# SCH_esp32-4g-gateway_2026-08-06.net
KiCad netlist of a schematic drawn in EasyEDA
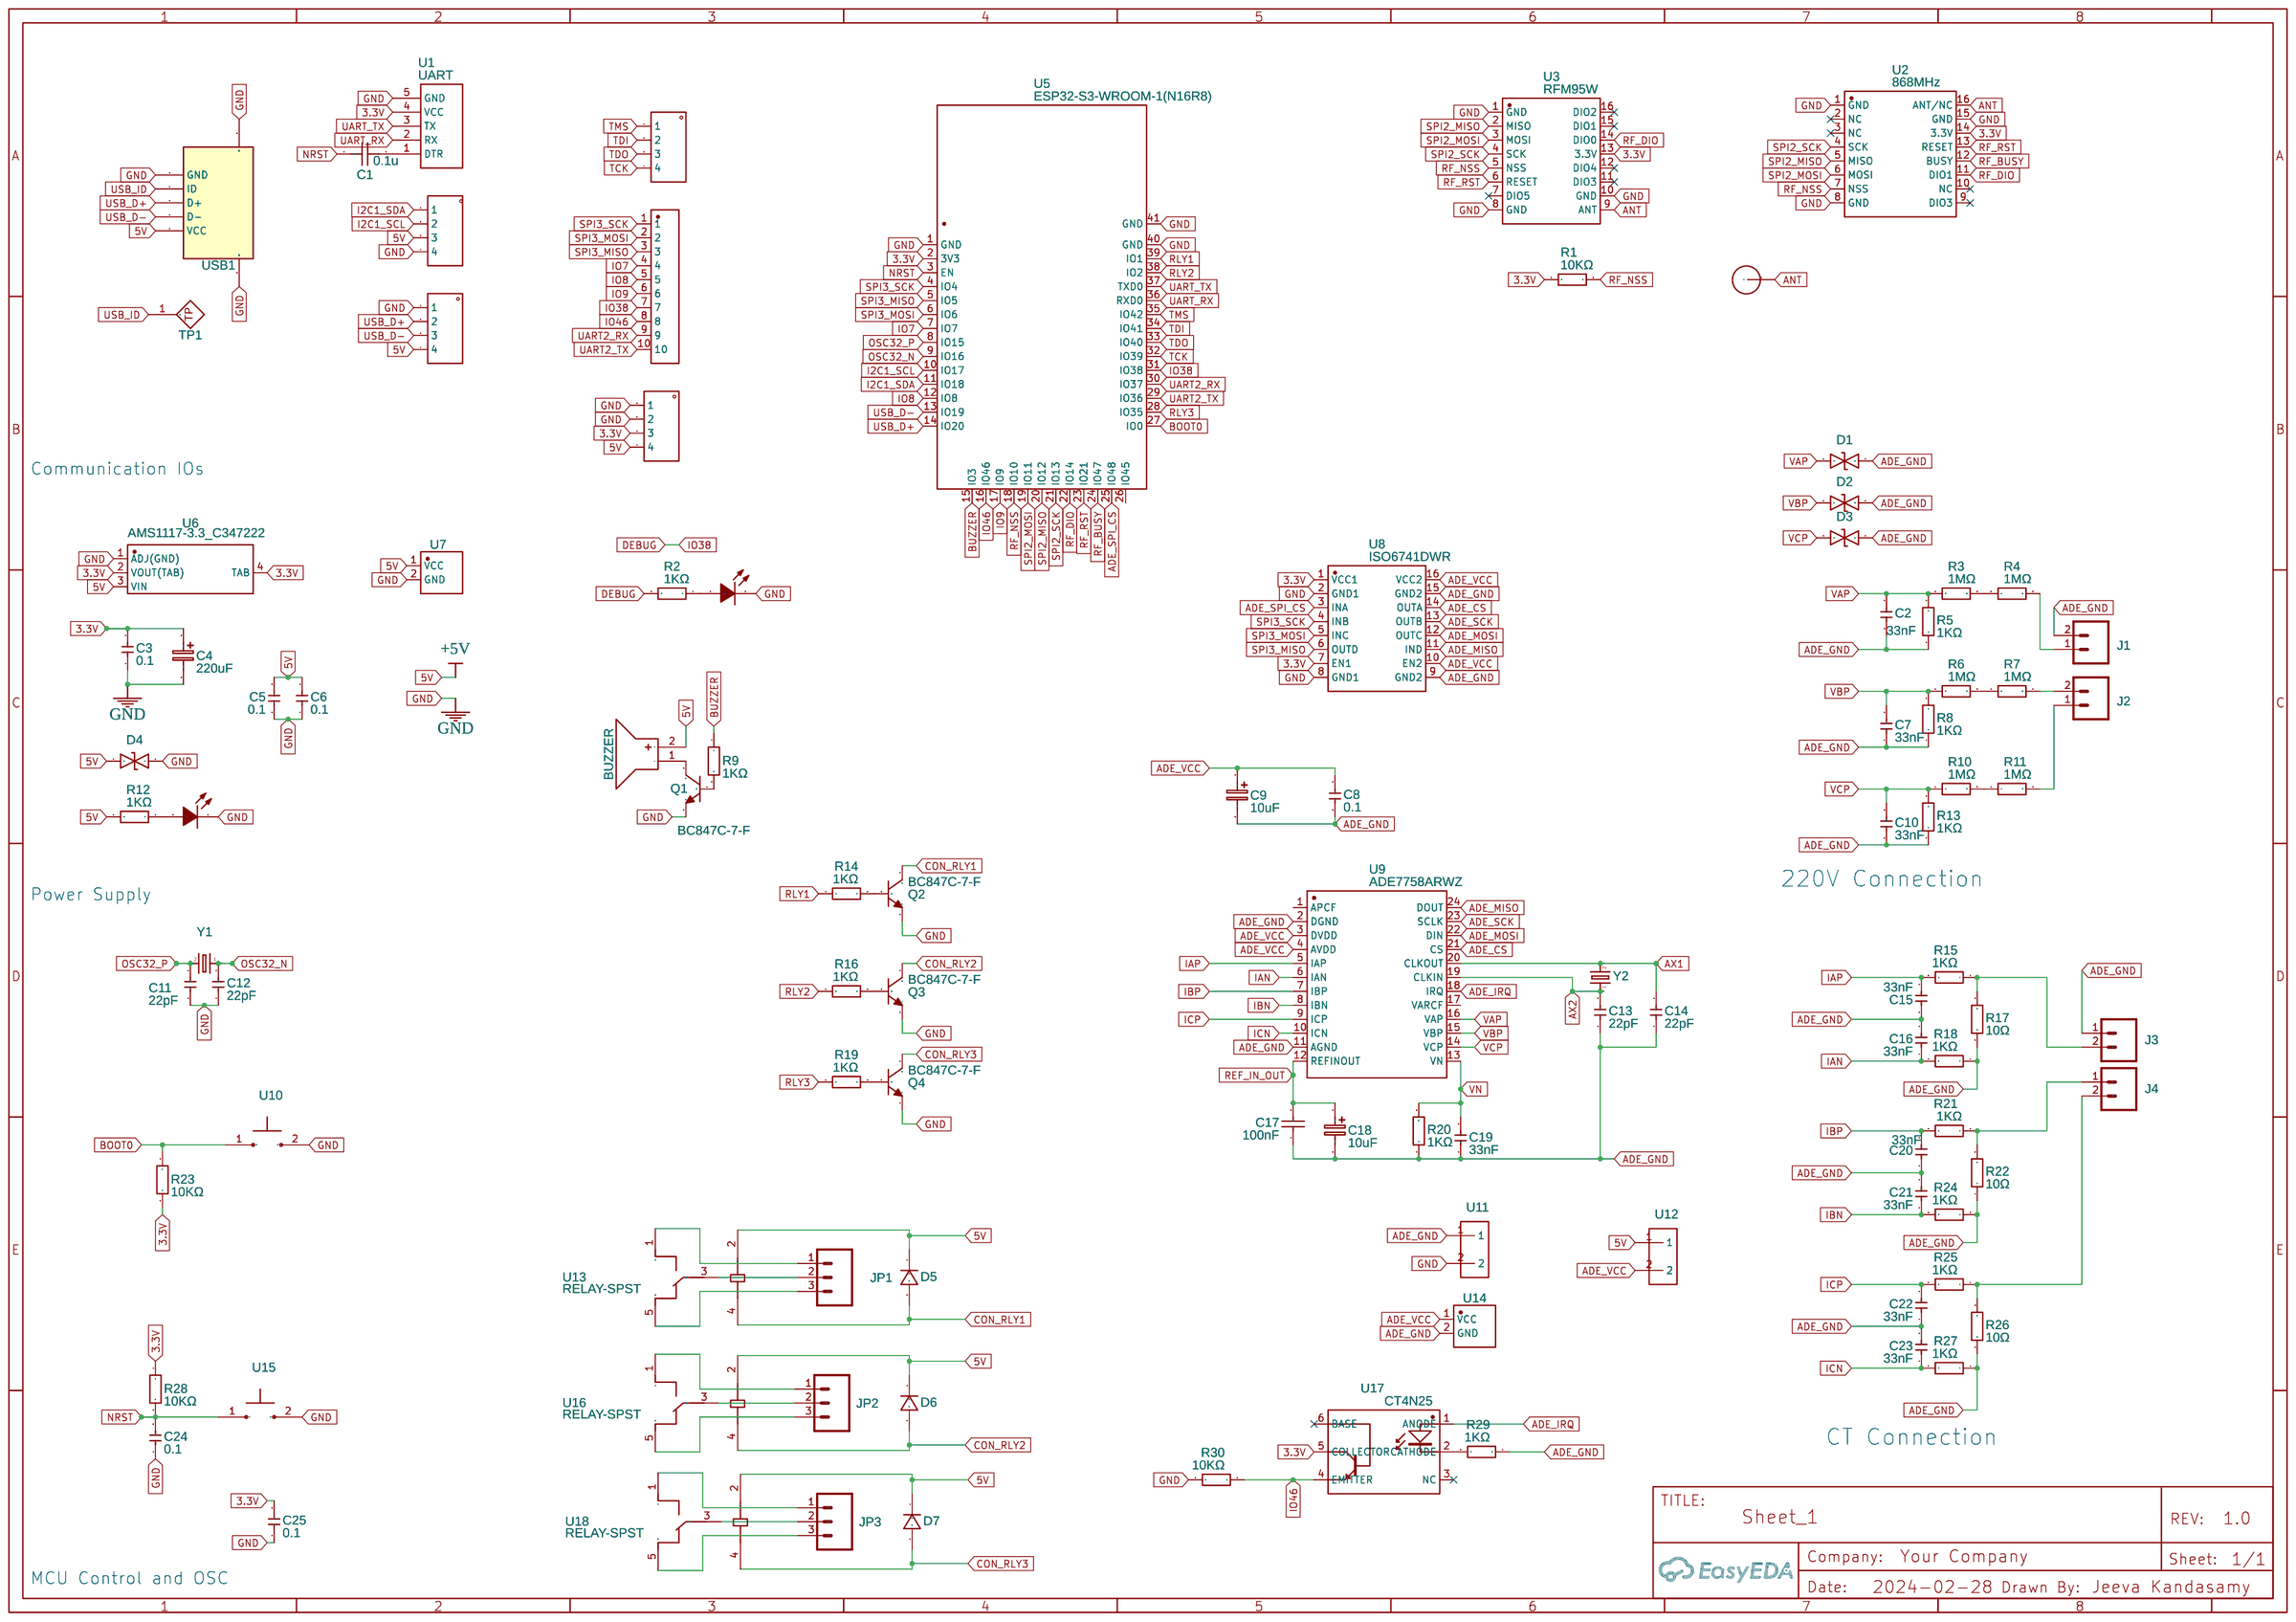
[diagram p0: schematic sheet]

(export (version "E")
  (design (tool "Eeschema 10.0.6"))
  (components
    (comp (ref "ANT1") (value "RFM12B_ANTENNA") (libsource (lib "") (part "RFM12B_ANTENNA")))
    (comp (ref "BUZZER")
      (value "BUZZER")
      (fields (field (name "Manufacturer Part") "buzzer"))
      (libsource (lib "") (part "BUZZER"))
    )
    (comp (ref "C1") (value "0.1u") (libsource (lib "") (part "C_0603_US")))
    (comp (ref "C2")
      (value "33nF")
      (fields (field (name "Manufacturer Part") "CC0603KRX7R9BB333"))
      (libsource (lib "") (part "Unknown_1345_-720"))
    )
    (comp (ref "C3")
      (value "0.1")
      (fields (field (name "Manufacturer Part") "CC0603JRNPO9BN220"))
      (libsource (lib "") (part "Unknown_85_-695"))
    )
    (comp (ref "C4")
      (value "220uF")
      (fields (field (name "Manufacturer Part") "JORGE TOURIS COMPANY"))
      (libsource (lib "") (part "My 10uF Capator"))
    )
    (comp (ref "C5")
      (value "0.1")
      (fields (field (name "Manufacturer Part") "CC0603JRNPO9BN220"))
      (libsource (lib "") (part "Unknown_190_-660"))
    )
    (comp (ref "C6")
      (value "0.1")
      (fields (field (name "Manufacturer Part") "CC0603JRNPO9BN220"))
      (libsource (lib "") (part "Unknown_210_-660"))
    )
    (comp (ref "C7")
      (value "33nF")
      (fields (field (name "Manufacturer Part") "CC0603KRX7R9BB333"))
      (libsource (lib "") (part "Unknown_1345_-640"))
    )
    (comp (ref "C8")
      (value "0.1")
      (fields (field (name "Manufacturer Part") "CC0603JRNPO9BN220"))
      (libsource (lib "") (part "Unknown_950_-590"))
    )
    (comp (ref "C9")
      (value "10uF")
      (fields (field (name "Manufacturer Part") "JORGE TOURIS COMPANY"))
      (libsource (lib "") (part "My 10uF Capator_2"))
    )
    (comp (ref "C10")
      (value "33nF")
      (fields (field (name "Manufacturer Part") "CC0603KRX7R9BB333"))
      (libsource (lib "") (part "Unknown_1345_-570"))
    )
    (comp (ref "C11")
      (value "22pF")
      (fields (field (name "Manufacturer Part") "CC0603JRNPO9BN220"))
      (libsource (lib "") (part "Unknown_130_-455"))
    )
    (comp (ref "C12")
      (value "22pF")
      (fields (field (name "Manufacturer Part") "CC0603JRNPO9BN220"))
      (libsource (lib "") (part "Unknown_150_-455"))
    )
    (comp (ref "C13")
      (value "22pF")
      (fields (field (name "Manufacturer Part") "CC0603JRNPO9BN220"))
      (libsource (lib "") (part "Unknown_1140_-435"))
    )
    (comp (ref "C14")
      (value "22pF")
      (fields (field (name "Manufacturer Part") "CC0603JRNPO9BN220"))
      (libsource (lib "") (part "Unknown_1180_-435"))
    )
    (comp (ref "C15")
      (value "33nF")
      (fields (field (name "Manufacturer Part") "CC0603KRX7R9BB333"))
      (libsource (lib "") (part "Unknown_1370_-435"))
    )
    (comp (ref "C16")
      (value "33nF")
      (fields (field (name "Manufacturer Part") "CC0603KRX7R9BB333"))
      (libsource (lib "") (part "Unknown_1370_-415"))
    )
    (comp (ref "C17")
      (value "100nF")
      (fields (field (name "Manufacturer Part") "0603B104K500NT") (field (name "Manufacturer") "FH"))
      (libsource (lib "") (part "Unknown_920_-355"))
    )
    (comp (ref "C18")
      (value "10uF")
      (fields (field (name "Manufacturer Part") "JORGE TOURIS COMPANY"))
      (libsource (lib "") (part "My 10uF Capator_1"))
    )
    (comp (ref "C19")
      (value "33nF")
      (fields (field (name "Manufacturer Part") "CC0603KRX7R9BB333"))
      (libsource (lib "") (part "Unknown_1040_-345"))
    )
    (comp (ref "C20")
      (value "33nF")
      (fields (field (name "Manufacturer Part") "CC0603KRX7R9BB333"))
      (libsource (lib "") (part "Unknown_1370_-335"))
    )
    (comp (ref "C21")
      (value "33nF")
      (fields (field (name "Manufacturer Part") "CC0603KRX7R9BB333"))
      (libsource (lib "") (part "Unknown_1370_-305"))
    )
    (comp (ref "C22")
      (value "33nF")
      (fields (field (name "Manufacturer Part") "CC0603KRX7R9BB333"))
      (libsource (lib "") (part "Unknown_1370_-225"))
    )
    (comp (ref "C23")
      (value "33nF")
      (fields (field (name "Manufacturer Part") "CC0603KRX7R9BB333"))
      (libsource (lib "") (part "Unknown_1370_-195"))
    )
    (comp (ref "C24")
      (value "0.1")
      (fields (field (name "Manufacturer Part") "CC0603JRNPO9BN220"))
      (libsource (lib "") (part "Unknown_105_-130"))
    )
    (comp (ref "C25")
      (value "0.1")
      (fields (field (name "Manufacturer Part") "CC0603JRNPO9BN220"))
      (libsource (lib "") (part "Unknown_190_-70"))
    )
    (comp (ref "CN1") (value "PINHEADER-4PIN") (libsource (lib "") (part "PINHEADER-4PIN")))
    (comp (ref "CN2") (value "PINHEADER-4PIN") (libsource (lib "") (part "PINHEADER-4PIN_1")))
    (comp (ref "CN3") (value "PINHEADER-4PIN") (libsource (lib "") (part "PINHEADER-4PIN")))
    (comp (ref "CN4") (value "PINHEADER-4PIN") (libsource (lib "") (part "PINHEADER-4PIN")))
    (comp (ref "D1")
      (value "P4SMA6.8CA_C139527")
      (fields (field (name "Manufacturer Part") "P4SMA6.8CA") (field (name "Manufacturer") "Yenji Elec"))
      (libsource (lib "") (part "P4SMA6.8CA_C139527"))
    )
    (comp (ref "D2")
      (value "P4SMA6.8CA_C139527")
      (fields (field (name "Manufacturer Part") "P4SMA6.8CA") (field (name "Manufacturer") "Yenji Elec"))
      (libsource (lib "") (part "P4SMA6.8CA_C139527"))
    )
    (comp (ref "D3")
      (value "P4SMA6.8CA_C139527")
      (fields (field (name "Manufacturer Part") "P4SMA6.8CA") (field (name "Manufacturer") "Yenji Elec"))
      (libsource (lib "") (part "P4SMA6.8CA_C139527"))
    )
    (comp (ref "D4")
      (value "P4SMA6.8CA_C139527")
      (fields (field (name "Manufacturer Part") "P4SMA6.8CA") (field (name "Manufacturer") "Yenji Elec"))
      (libsource (lib "") (part "P4SMA6.8CA_C139527"))
    )
    (comp (ref "D5")
      (value "1N4007GU")
      (fields (field (name "Manufacturer") "DIYI Elec Tech"))
      (libsource (lib "") (part "1N4007GU"))
    )
    (comp (ref "D6")
      (value "1N4007GU")
      (fields (field (name "Manufacturer") "DIYI Elec Tech"))
      (libsource (lib "") (part "1N4007GU"))
    )
    (comp (ref "D7")
      (value "1N4007GU")
      (fields (field (name "Manufacturer") "DIYI Elec Tech"))
      (libsource (lib "") (part "1N4007GU"))
    )
    (comp (ref "DEBUG")
      (value "3ARB9HCB")
      (fields (field (name "Manufacturer") "KENTO"))
      (libsource (lib "") (part "3ARB9HCB"))
    )
    (comp (ref "J1") (value "M02-SCREW-5MM") (libsource (lib "") (part "M02-SCREW-5MM_1")))
    (comp (ref "J2") (value "M02-SCREW-5MM") (libsource (lib "") (part "M02-SCREW-5MM_1")))
    (comp (ref "J3") (value "M02-SCREW-5MM") (libsource (lib "") (part "M02-SCREW-5MM")))
    (comp (ref "J4") (value "M02-SCREW-5MM") (libsource (lib "") (part "M02-SCREW-5MM")))
    (comp (ref "JP1") (value "M03-SCREW-5MM") (libsource (lib "") (part "M03-SCREW-5MM")))
    (comp (ref "JP2") (value "M03-SCREW-5MM") (libsource (lib "") (part "M03-SCREW-5MM")))
    (comp (ref "JP3") (value "M03-SCREW-5MM") (libsource (lib "") (part "M03-SCREW-5MM")))
    (comp (ref "POWER")
      (value "3ARB9HCB")
      (fields (field (name "Manufacturer") "KENTO"))
      (libsource (lib "") (part "3ARB9HCB_1"))
    )
    (comp (ref "Q1")
      (value "BC847C-7-F")
      (fields (field (name "Manufacturer") "DIODES(美台)"))
      (libsource (lib "") (part "BC847C-7-F_1"))
    )
    (comp (ref "Q2")
      (value "BC847C-7-F")
      (fields (field (name "Manufacturer") "DIODES(美台)"))
      (libsource (lib "") (part "BC847C-7-F"))
    )
    (comp (ref "Q3")
      (value "BC847C-7-F")
      (fields (field (name "Manufacturer") "DIODES(美台)"))
      (libsource (lib "") (part "BC847C-7-F"))
    )
    (comp (ref "Q4")
      (value "BC847C-7-F")
      (fields (field (name "Manufacturer") "DIODES(美台)"))
      (libsource (lib "") (part "BC847C-7-F"))
    )
    (comp (ref "R1")
      (value "10KΩ")
      (fields (field (name "Manufacturer Part") "0603WAF1001T5E") (field (name "Manufacturer") "UniOhm"))
      (libsource (lib "") (part "Unknown_1120_-955"))
    )
    (comp (ref "R2")
      (value "1KΩ")
      (fields (field (name "Manufacturer Part") "0603WAF1001T5E") (field (name "Manufacturer") "UniOhm"))
      (libsource (lib "") (part "Unknown_475_-730"))
    )
    (comp (ref "R3")
      (value "1MΩ")
      (fields (field (name "Manufacturer Part") "0603WAF1004T5E") (field (name "Manufacturer") "UniOhm"))
      (libsource (lib "") (part "Unknown_1395_-730"))
    )
    (comp (ref "R4")
      (value "1MΩ")
      (fields (field (name "Manufacturer Part") "0603WAF1004T5E") (field (name "Manufacturer") "UniOhm"))
      (libsource (lib "") (part "Unknown_1435_-730"))
    )
    (comp (ref "R5")
      (value "1KΩ")
      (fields (field (name "Manufacturer Part") "0603WAF1001T5E") (field (name "Manufacturer") "UniOhm"))
      (libsource (lib "") (part "Unknown_1375_-710"))
    )
    (comp (ref "R6")
      (value "1MΩ")
      (fields (field (name "Manufacturer Part") "0603WAF1004T5E") (field (name "Manufacturer") "UniOhm"))
      (libsource (lib "") (part "Unknown_1395_-660"))
    )
    (comp (ref "R7")
      (value "1MΩ")
      (fields (field (name "Manufacturer Part") "0603WAF1004T5E") (field (name "Manufacturer") "UniOhm"))
      (libsource (lib "") (part "Unknown_1435_-660"))
    )
    (comp (ref "R8")
      (value "1KΩ")
      (fields (field (name "Manufacturer Part") "0603WAF1001T5E") (field (name "Manufacturer") "UniOhm"))
      (libsource (lib "") (part "Unknown_1375_-640"))
    )
    (comp (ref "R9")
      (value "1KΩ")
      (fields (field (name "Manufacturer Part") "0603WAF1001T5E") (field (name "Manufacturer") "UniOhm"))
      (libsource (lib "") (part "Unknown_505_-610"))
    )
    (comp (ref "R10")
      (value "1MΩ")
      (fields (field (name "Manufacturer Part") "0603WAF1004T5E") (field (name "Manufacturer") "UniOhm"))
      (libsource (lib "") (part "Unknown_1395_-590"))
    )
    (comp (ref "R11")
      (value "1MΩ")
      (fields (field (name "Manufacturer Part") "0603WAF1004T5E") (field (name "Manufacturer") "UniOhm"))
      (libsource (lib "") (part "Unknown_1435_-590"))
    )
    (comp (ref "R12")
      (value "1KΩ")
      (fields (field (name "Manufacturer Part") "0603WAF1001T5E") (field (name "Manufacturer") "UniOhm"))
      (libsource (lib "") (part "Unknown_90_-570"))
    )
    (comp (ref "R13")
      (value "1KΩ")
      (fields (field (name "Manufacturer Part") "0603WAF1001T5E") (field (name "Manufacturer") "UniOhm"))
      (libsource (lib "") (part "Unknown_1375_-570"))
    )
    (comp (ref "R14")
      (value "1KΩ")
      (fields (field (name "Manufacturer Part") "0603WAF1001T5E") (field (name "Manufacturer") "UniOhm"))
      (libsource (lib "") (part "Unknown_600_-515"))
    )
    (comp (ref "R15")
      (value "1KΩ")
      (fields (field (name "Manufacturer Part") "0603WAF1001T5E") (field (name "Manufacturer") "UniOhm"))
      (libsource (lib "") (part "Unknown_1390_-455"))
    )
    (comp (ref "R16")
      (value "1KΩ")
      (fields (field (name "Manufacturer Part") "0603WAF1001T5E") (field (name "Manufacturer") "UniOhm"))
      (libsource (lib "") (part "Unknown_600_-445"))
    )
    (comp (ref "R17")
      (value "10Ω")
      (fields (field (name "Manufacturer Part") "0603WAF100JT5E") (field (name "Manufacturer") "UniOhm"))
      (libsource (lib "") (part "Unknown_1410_-425"))
    )
    (comp (ref "R18")
      (value "1KΩ")
      (fields (field (name "Manufacturer Part") "0603WAF1001T5E") (field (name "Manufacturer") "UniOhm"))
      (libsource (lib "") (part "Unknown_1390_-395"))
    )
    (comp (ref "R19")
      (value "1KΩ")
      (fields (field (name "Manufacturer Part") "0603WAF1001T5E") (field (name "Manufacturer") "UniOhm"))
      (libsource (lib "") (part "Unknown_600_-380"))
    )
    (comp (ref "R20")
      (value "1KΩ")
      (fields (field (name "Manufacturer Part") "0603WAF1001T5E") (field (name "Manufacturer") "UniOhm"))
      (libsource (lib "") (part "Unknown_1010_-345"))
    )
    (comp (ref "R21")
      (value "1KΩ")
      (fields (field (name "Manufacturer Part") "0603WAF1001T5E") (field (name "Manufacturer") "UniOhm"))
      (libsource (lib "") (part "Unknown_1390_-345"))
    )
    (comp (ref "R22")
      (value "10Ω")
      (fields (field (name "Manufacturer Part") "0603WAF100JT5E") (field (name "Manufacturer") "UniOhm"))
      (libsource (lib "") (part "Unknown_1410_-315"))
    )
    (comp (ref "R23")
      (value "10KΩ")
      (fields (field (name "Manufacturer Part") "0603WAF1001T5E") (field (name "Manufacturer") "UniOhm"))
      (libsource (lib "") (part "Unknown_110_-310"))
    )
    (comp (ref "R24")
      (value "1KΩ")
      (fields (field (name "Manufacturer Part") "0603WAF1001T5E") (field (name "Manufacturer") "UniOhm"))
      (libsource (lib "") (part "Unknown_1390_-285"))
    )
    (comp (ref "R25")
      (value "1KΩ")
      (fields (field (name "Manufacturer Part") "0603WAF1001T5E") (field (name "Manufacturer") "UniOhm"))
      (libsource (lib "") (part "Unknown_1390_-235"))
    )
    (comp (ref "R26")
      (value "10Ω")
      (fields (field (name "Manufacturer Part") "0603WAF100JT5E") (field (name "Manufacturer") "UniOhm"))
      (libsource (lib "") (part "Unknown_1410_-205"))
    )
    (comp (ref "R27")
      (value "1KΩ")
      (fields (field (name "Manufacturer Part") "0603WAF1001T5E") (field (name "Manufacturer") "UniOhm"))
      (libsource (lib "") (part "Unknown_1390_-175"))
    )
    (comp (ref "R28")
      (value "10KΩ")
      (fields (field (name "Manufacturer Part") "0603WAF1001T5E") (field (name "Manufacturer") "UniOhm"))
      (libsource (lib "") (part "Unknown_105_-160"))
    )
    (comp (ref "R29")
      (value "1KΩ")
      (fields (field (name "Manufacturer Part") "0603WAF1001T5E") (field (name "Manufacturer") "UniOhm"))
      (libsource (lib "") (part "Unknown_1055_-115"))
    )
    (comp (ref "R30")
      (value "10KΩ")
      (fields (field (name "Manufacturer Part") "0603WAF1001T5E") (field (name "Manufacturer") "UniOhm"))
      (libsource (lib "") (part "Unknown_865_-95"))
    )
    (comp (ref "TP1") (value "Test Point") (libsource (lib "") (part "Test Point")))
    (comp (ref "U1")
      (value "UART")
      (fields (field (name "Manufacturer Part") "CP2102 UART"))
      (libsource (lib "") (part "Arduino-UART"))
    )
    (comp (ref "U2")
      (value "868MHz")
      (fields
        (field (name "Manufacturer Part") "DL-LLCC68-S-868")
        (field (name "Manufacturer") "DreamLNK(骏晔科技)")
      )
      (libsource (lib "") (part "DL-LLCC68-S-868"))
    )
    (comp (ref "U3") (value "RFM95W") (libsource (lib "") (part "RFM95W")))
    (comp (ref "U4")
      (value "Pin Header 1x10Pin 2.54mm 10P")
      (libsource (lib "") (part "Pin Header 1x10Pin 2.54mm 10P"))
    )
    (comp (ref "U5")
      (value "ESP32-S3-WROOM-1(N16R8)")
      (fields
        (field (name "Manufacturer Part") "ESP32-S3-WROOM-1-N16R8")
        (field (name "Manufacturer") "ESPRESSIF(乐鑫)")
      )
      (libsource (lib "") (part "ESP32-S3-WROOM-1(N16R8)"))
    )
    (comp (ref "U6")
      (value "AMS1117-3.3_C347222")
      (fields
        (field (name "Manufacturer Part") "AMS1117-3.3")
        (field (name "Manufacturer") "Youtai Semiconductor Co., Ltd.")
      )
      (libsource (lib "") (part "AMS1117-3.3_C347222"))
    )
    (comp (ref "U7") (value "2 Pin Header") (libsource (lib "") (part "2 Pin Header")))
    (comp (ref "U8") (value "ISO6741DWR") (libsource (lib "") (part "ISO6741DWR")))
    (comp (ref "U9")
      (value "ADE7758ARWZ")
      (fields (field (name "Manufacturer Part") "?"))
      (libsource (lib "") (part "Unknown_980_-515"))
    )
    (comp (ref "U10")
      (value "SMD Tactile Switch 3x6x2.5")
      (libsource (lib "") (part "SMD Tactile Switch 3x6x2.5"))
    )
    (comp (ref "U11") (value "Jumper - 5MM") (libsource (lib "") (part "Jumper - 5MM")))
    (comp (ref "U12") (value "Jumper - 5MM") (libsource (lib "") (part "Jumper - 5MM")))
    (comp (ref "U13")
      (value "RELAY-SPST")
      (fields (field (name "Manufacturer Part") "Relay-SPST"))
      (libsource (lib "") (part "RELAY-SPST"))
    )
    (comp (ref "U14") (value "2 Pin Header") (libsource (lib "") (part "2 Pin Header")))
    (comp (ref "U15")
      (value "SMD Tactile Switch 3x6x2.5")
      (libsource (lib "") (part "SMD Tactile Switch 3x6x2.5"))
    )
    (comp (ref "U16")
      (value "RELAY-SPST")
      (fields (field (name "Manufacturer Part") "Relay-SPST"))
      (libsource (lib "") (part "RELAY-SPST"))
    )
    (comp (ref "U17")
      (value "CT4N25")
      (fields (field (name "Manufacturer Part") "4N25") (field (name "Manufacturer") "CT MICRO"))
      (libsource (lib "") (part "CT4N25"))
    )
    (comp (ref "U18")
      (value "RELAY-SPST")
      (fields (field (name "Manufacturer Part") "Relay-SPST"))
      (libsource (lib "") (part "RELAY-SPST"))
    )
    (comp (ref "USB1")
      (value "U-F-M5SW-Y-3")
      (fields (field (name "Manufacturer") "韩国韩荣"))
      (libsource (lib "") (part "U-F-M5SW-Y-3"))
    )
    (comp (ref "Y1")
      (value "CRYSTAL 10MHz")
      (fields (field (name "Manufacturer Part") "?"))
      (libsource (lib "") (part "Unknown_140_-465"))
    )
    (comp (ref "Y2")
      (value "CRYSTAL 10MHz")
      (fields (field (name "Manufacturer Part") "?"))
      (libsource (lib "") (part "Unknown_1140_-455"))
    )
  )
  (nets
    (net (code "1") (name "3.3V") (class "Default")
      (node (ref "C25") (pin "2") (pinfunction "2_2") (pintype "unspecified"))
      (node (ref "C3") (pin "2") (pinfunction "2_2") (pintype "unspecified"))
      (node (ref "C4") (pin "1") (pinfunction "1_1") (pintype "unspecified"))
      (node (ref "CN4") (pin "3") (pinfunction "3_3") (pintype "input"))
      (node (ref "R1") (pin "2") (pinfunction "2_2") (pintype "input"))
      (node (ref "R23") (pin "2") (pinfunction "2_2") (pintype "input"))
      (node (ref "R28") (pin "1") (pinfunction "1_1") (pintype "input"))
      (node (ref "U1") (pin "4") (pinfunction "VCC_4") (pintype "passive"))
      (node (ref "U17") (pin "5") (pinfunction "COLLECTOR_5") (pintype "unspecified"))
      (node (ref "U2") (pin "14") (pinfunction "3.3V_14") (pintype "unspecified"))
      (node (ref "U3") (pin "13") (pinfunction "3.3V_13") (pintype "unspecified"))
      (node (ref "U5") (pin "2") (pinfunction "3V3_2") (pintype "unspecified"))
      (node (ref "U6") (pin "2") (pinfunction "VOUT(TAB)_2") (pintype "unspecified"))
      (node (ref "U6") (pin "4") (pinfunction "TAB_4") (pintype "unspecified"))
      (node (ref "U8") (pin "1") (pinfunction "VCC1_1") (pintype "unspecified"))
      (node (ref "U8") (pin "7") (pinfunction "EN1_7") (pintype "unspecified"))
    )
    (net (code "2") (name "5V") (class "Default")
      (node (ref "BUZZER") (pin "2") (pinfunction "+_2") (pintype "unspecified"))
      (node (ref "C5") (pin "2") (pinfunction "2_2") (pintype "unspecified"))
      (node (ref "C6") (pin "2") (pinfunction "2_2") (pintype "unspecified"))
      (node (ref "CN2") (pin "3") (pinfunction "3_3") (pintype "input"))
      (node (ref "CN3") (pin "4") (pinfunction "4_4") (pintype "input"))
      (node (ref "CN4") (pin "4") (pinfunction "4_4") (pintype "input"))
      (node (ref "D4") (pin "2") (pinfunction "2_2") (pintype "unspecified"))
      (node (ref "D5") (pin "1") (pinfunction "1_1") (pintype "unspecified"))
      (node (ref "D6") (pin "1") (pinfunction "1_1") (pintype "unspecified"))
      (node (ref "D7") (pin "1") (pinfunction "1_1") (pintype "unspecified"))
      (node (ref "R12") (pin "2") (pinfunction "2_2") (pintype "input"))
      (node (ref "U12") (pin "1") (pinfunction "1_1") (pintype "unspecified"))
      (node (ref "U13") (pin "2") (pinfunction "2_2") (pintype "unspecified"))
      (node (ref "U16") (pin "2") (pinfunction "2_2") (pintype "unspecified"))
      (node (ref "U18") (pin "2") (pinfunction "2_2") (pintype "unspecified"))
      (node (ref "U6") (pin "3") (pinfunction "VIN_3") (pintype "unspecified"))
      (node (ref "U7") (pin "1") (pinfunction "VCC_1") (pintype "unspecified"))
      (node (ref "USB1") (pin "1") (pinfunction "VCC_1") (pintype "input"))
    )
    (net (code "3") (name "ADE_CS") (class "Default")
      (node (ref "U8") (pin "14") (pinfunction "OUTA_14") (pintype "unspecified"))
      (node (ref "U9") (pin "21") (pinfunction "CS_21") (pintype "unspecified"))
    )
    (net (code "4") (name "ADE_GND") (class "Default")
      (node (ref "C10") (pin "1") (pinfunction "1_1") (pintype "unspecified"))
      (node (ref "C13") (pin "1") (pinfunction "1_1") (pintype "unspecified"))
      (node (ref "C14") (pin "1") (pinfunction "1_1") (pintype "unspecified"))
      (node (ref "C15") (pin "2") (pinfunction "2_2") (pintype "unspecified"))
      (node (ref "C16") (pin "2") (pinfunction "2_2") (pintype "unspecified"))
      (node (ref "C17") (pin "1") (pinfunction "1_1") (pintype "input"))
      (node (ref "C18") (pin "2") (pinfunction "2_2") (pintype "unspecified"))
      (node (ref "C19") (pin "1") (pinfunction "1_1") (pintype "unspecified"))
      (node (ref "C2") (pin "1") (pinfunction "1_1") (pintype "unspecified"))
      (node (ref "C20") (pin "1") (pinfunction "1_1") (pintype "unspecified"))
      (node (ref "C21") (pin "2") (pinfunction "2_2") (pintype "unspecified"))
      (node (ref "C22") (pin "1") (pinfunction "1_1") (pintype "unspecified"))
      (node (ref "C23") (pin "2") (pinfunction "2_2") (pintype "unspecified"))
      (node (ref "C7") (pin "1") (pinfunction "1_1") (pintype "unspecified"))
      (node (ref "C8") (pin "1") (pinfunction "1_1") (pintype "unspecified"))
      (node (ref "C9") (pin "2") (pinfunction "2_2") (pintype "unspecified"))
      (node (ref "D1") (pin "1") (pinfunction "1_1") (pintype "unspecified"))
      (node (ref "D2") (pin "1") (pinfunction "1_1") (pintype "unspecified"))
      (node (ref "D3") (pin "1") (pinfunction "1_1") (pintype "unspecified"))
      (node (ref "J1") (pin "2") (pinfunction "2_2") (pintype "bidirectional"))
      (node (ref "J3") (pin "1") (pinfunction "1_1") (pintype "bidirectional"))
      (node (ref "R13") (pin "1") (pinfunction "1_1") (pintype "input"))
      (node (ref "R17") (pin "1") (pinfunction "1_1") (pintype "input"))
      (node (ref "R18") (pin "1") (pinfunction "1_1") (pintype "input"))
      (node (ref "R20") (pin "1") (pinfunction "1_1") (pintype "input"))
      (node (ref "R22") (pin "1") (pinfunction "1_1") (pintype "input"))
      (node (ref "R24") (pin "1") (pinfunction "1_1") (pintype "input"))
      (node (ref "R26") (pin "1") (pinfunction "1_1") (pintype "input"))
      (node (ref "R27") (pin "1") (pinfunction "1_1") (pintype "input"))
      (node (ref "R29") (pin "1") (pinfunction "1_1") (pintype "input"))
      (node (ref "R5") (pin "1") (pinfunction "1_1") (pintype "input"))
      (node (ref "R8") (pin "1") (pinfunction "1_1") (pintype "input"))
      (node (ref "U11") (pin "1") (pinfunction "1_1") (pintype "unspecified"))
      (node (ref "U14") (pin "2") (pinfunction "GND_2") (pintype "unspecified"))
      (node (ref "U8") (pin "15") (pinfunction "GND2_15") (pintype "unspecified"))
      (node (ref "U8") (pin "9") (pinfunction "GND2_9") (pintype "unspecified"))
      (node (ref "U9") (pin "11") (pinfunction "AGND_11") (pintype "unspecified"))
      (node (ref "U9") (pin "2") (pinfunction "DGND_2") (pintype "unspecified"))
    )
    (net (code "5") (name "ADE_IRQ") (class "Default")
      (node (ref "U17") (pin "1") (pinfunction "ANODE_1") (pintype "unspecified"))
      (node (ref "U9") (pin "18") (pinfunction "IRQ_18") (pintype "unspecified"))
    )
    (net (code "6") (name "ADE_MISO") (class "Default")
      (node (ref "U8") (pin "11") (pinfunction "IND_11") (pintype "unspecified"))
      (node (ref "U9") (pin "24") (pinfunction "DOUT_24") (pintype "unspecified"))
    )
    (net (code "7") (name "ADE_MOSI") (class "Default")
      (node (ref "U8") (pin "12") (pinfunction "OUTC_12") (pintype "unspecified"))
      (node (ref "U9") (pin "22") (pinfunction "DIN_22") (pintype "unspecified"))
    )
    (net (code "8") (name "ADE_SCK") (class "Default")
      (node (ref "U8") (pin "13") (pinfunction "OUTB_13") (pintype "unspecified"))
      (node (ref "U9") (pin "23") (pinfunction "SCLK_23") (pintype "unspecified"))
    )
    (net (code "9") (name "ADE_SPI_CS") (class "Default")
      (node (ref "U5") (pin "25") (pinfunction "IO48_25") (pintype "unspecified"))
      (node (ref "U8") (pin "3") (pinfunction "INA_3") (pintype "unspecified"))
    )
    (net (code "10") (name "ADE_VCC") (class "Default")
      (node (ref "C8") (pin "2") (pinfunction "2_2") (pintype "unspecified"))
      (node (ref "C9") (pin "1") (pinfunction "1_1") (pintype "unspecified"))
      (node (ref "U12") (pin "2") (pinfunction "2_2") (pintype "unspecified"))
      (node (ref "U14") (pin "1") (pinfunction "VCC_1") (pintype "unspecified"))
      (node (ref "U8") (pin "10") (pinfunction "EN2_10") (pintype "unspecified"))
      (node (ref "U8") (pin "16") (pinfunction "VCC2_16") (pintype "unspecified"))
      (node (ref "U9") (pin "3") (pinfunction "DVDD_3") (pintype "unspecified"))
      (node (ref "U9") (pin "4") (pinfunction "AVDD_4") (pintype "unspecified"))
    )
    (net (code "11") (name "ANT") (class "Default")
      (node (ref "ANT1") (pin "P$1") (pinfunction "1_P$1") (pintype "bidirectional"))
      (node (ref "U2") (pin "16") (pinfunction "ANT/NC_16") (pintype "unspecified"))
      (node (ref "U3") (pin "9") (pinfunction "ANT_9") (pintype "unspecified"))
    )
    (net (code "12") (name "AX1") (class "Default")
      (node (ref "C14") (pin "2") (pinfunction "2_2") (pintype "unspecified"))
      (node (ref "U9") (pin "20") (pinfunction "CLKOUT_20") (pintype "unspecified"))
      (node (ref "Y2") (pin "2") (pinfunction "2_2") (pintype "unspecified"))
    )
    (net (code "13") (name "AX2") (class "Default")
      (node (ref "C13") (pin "2") (pinfunction "2_2") (pintype "unspecified"))
      (node (ref "U9") (pin "19") (pinfunction "CLKIN_19") (pintype "unspecified"))
      (node (ref "Y2") (pin "1") (pinfunction "1_1") (pintype "unspecified"))
    )
    (net (code "14") (name "BOOT0") (class "Default")
      (node (ref "R23") (pin "1") (pinfunction "1_1") (pintype "input"))
      (node (ref "U10") (pin "1") (pinfunction "1_1") (pintype "unspecified"))
      (node (ref "U5") (pin "27") (pinfunction "IO0_27") (pintype "unspecified"))
    )
    (net (code "15") (name "BUZZER") (class "Default")
      (node (ref "R9") (pin "1") (pinfunction "1_1") (pintype "input"))
      (node (ref "U5") (pin "15") (pinfunction "IO3_15") (pintype "unspecified"))
    )
    (net (code "16") (name "CON_RLY1") (class "Default")
      (node (ref "D5") (pin "2") (pinfunction "2_2") (pintype "unspecified"))
      (node (ref "Q2") (pin "3") (pinfunction "C_3") (pintype "unspecified"))
      (node (ref "U13") (pin "4") (pinfunction "4_4") (pintype "unspecified"))
    )
    (net (code "17") (name "CON_RLY2") (class "Default")
      (node (ref "D6") (pin "2") (pinfunction "2_2") (pintype "unspecified"))
      (node (ref "Q3") (pin "3") (pinfunction "C_3") (pintype "unspecified"))
      (node (ref "U16") (pin "4") (pinfunction "4_4") (pintype "unspecified"))
    )
    (net (code "18") (name "CON_RLY3") (class "Default")
      (node (ref "D7") (pin "2") (pinfunction "2_2") (pintype "unspecified"))
      (node (ref "Q4") (pin "3") (pinfunction "C_3") (pintype "unspecified"))
      (node (ref "U18") (pin "4") (pinfunction "4_4") (pintype "unspecified"))
    )
    (net (code "19") (name "DEBUG") (class "Default")
      (node (ref "R2") (pin "2") (pinfunction "2_2") (pintype "input"))
      (node (ref "U4") (pin "7") (pinfunction "7_7") (pintype "unspecified"))
      (node (ref "U5") (pin "31") (pinfunction "IO38_31") (pintype "unspecified"))
    )
    (net (code "20") (name "GND") (class "Default")
      (node (ref "C11") (pin "1") (pinfunction "1_1") (pintype "unspecified"))
      (node (ref "C12") (pin "1") (pinfunction "1_1") (pintype "unspecified"))
      (node (ref "C24") (pin "1") (pinfunction "1_1") (pintype "unspecified"))
      (node (ref "C25") (pin "1") (pinfunction "1_1") (pintype "unspecified"))
      (node (ref "C3") (pin "1") (pinfunction "1_1") (pintype "unspecified"))
      (node (ref "C4") (pin "2") (pinfunction "2_2") (pintype "unspecified"))
      (node (ref "C5") (pin "1") (pinfunction "1_1") (pintype "unspecified"))
      (node (ref "C6") (pin "1") (pinfunction "1_1") (pintype "unspecified"))
      (node (ref "CN2") (pin "4") (pinfunction "4_4") (pintype "input"))
      (node (ref "CN3") (pin "1") (pinfunction "1_1") (pintype "input"))
      (node (ref "CN4") (pin "1") (pinfunction "1_1") (pintype "input"))
      (node (ref "CN4") (pin "2") (pinfunction "2_2") (pintype "input"))
      (node (ref "D4") (pin "1") (pinfunction "1_1") (pintype "unspecified"))
      (node (ref "DEBUG") (pin "2") (pinfunction "K_2") (pintype "unspecified"))
      (node (ref "POWER") (pin "2") (pinfunction "K_2") (pintype "unspecified"))
      (node (ref "Q1") (pin "2") (pinfunction "E_2") (pintype "unspecified"))
      (node (ref "Q2") (pin "2") (pinfunction "E_2") (pintype "unspecified"))
      (node (ref "Q3") (pin "2") (pinfunction "E_2") (pintype "unspecified"))
      (node (ref "Q4") (pin "2") (pinfunction "E_2") (pintype "unspecified"))
      (node (ref "R30") (pin "2") (pinfunction "2_2") (pintype "input"))
      (node (ref "U1") (pin "5") (pinfunction "GND_5") (pintype "passive"))
      (node (ref "U10") (pin "2") (pinfunction "2_2") (pintype "unspecified"))
      (node (ref "U11") (pin "2") (pinfunction "2_2") (pintype "unspecified"))
      (node (ref "U15") (pin "2") (pinfunction "2_2") (pintype "unspecified"))
      (node (ref "U2") (pin "1") (pinfunction "GND_1") (pintype "unspecified"))
      (node (ref "U2") (pin "15") (pinfunction "GND_15") (pintype "unspecified"))
      (node (ref "U2") (pin "8") (pinfunction "GND_8") (pintype "unspecified"))
      (node (ref "U3") (pin "1") (pinfunction "GND_1") (pintype "unspecified"))
      (node (ref "U3") (pin "10") (pinfunction "GND_10") (pintype "unspecified"))
      (node (ref "U3") (pin "8") (pinfunction "GND_8") (pintype "unspecified"))
      (node (ref "U5") (pin "1") (pinfunction "GND_1") (pintype "unspecified"))
      (node (ref "U5") (pin "40") (pinfunction "GND_40") (pintype "unspecified"))
      (node (ref "U5") (pin "41") (pinfunction "GND_41") (pintype "unspecified"))
      (node (ref "U6") (pin "1") (pinfunction "ADJ(GND)_1") (pintype "unspecified"))
      (node (ref "U7") (pin "2") (pinfunction "GND_2") (pintype "unspecified"))
      (node (ref "U8") (pin "2") (pinfunction "GND1_2") (pintype "unspecified"))
      (node (ref "U8") (pin "8") (pinfunction "GND1_8") (pintype "unspecified"))
      (node (ref "USB1") (pin "0") (pinfunction "SHLD_0") (pintype "input"))
      (node (ref "USB1") (pin "5") (pinfunction "GND_5") (pintype "input"))
    )
    (net (code "21") (name "I2C1_SCL") (class "Default")
      (node (ref "CN2") (pin "2") (pinfunction "2_2") (pintype "input"))
      (node (ref "U5") (pin "10") (pinfunction "IO17_10") (pintype "unspecified"))
    )
    (net (code "22") (name "I2C1_SDA") (class "Default")
      (node (ref "CN2") (pin "1") (pinfunction "1_1") (pintype "input"))
      (node (ref "U5") (pin "11") (pinfunction "IO18_11") (pintype "unspecified"))
    )
    (net (code "23") (name "IAN") (class "Default")
      (node (ref "C16") (pin "1") (pinfunction "1_1") (pintype "unspecified"))
      (node (ref "R18") (pin "2") (pinfunction "2_2") (pintype "input"))
      (node (ref "U9") (pin "6") (pinfunction "IAN_6") (pintype "unspecified"))
    )
    (net (code "24") (name "IAP") (class "Default")
      (node (ref "C15") (pin "1") (pinfunction "1_1") (pintype "unspecified"))
      (node (ref "R15") (pin "2") (pinfunction "2_2") (pintype "input"))
      (node (ref "U9") (pin "5") (pinfunction "IAP_5") (pintype "unspecified"))
    )
    (net (code "25") (name "IBN") (class "Default")
      (node (ref "C21") (pin "1") (pinfunction "1_1") (pintype "unspecified"))
      (node (ref "R24") (pin "2") (pinfunction "2_2") (pintype "input"))
      (node (ref "U9") (pin "8") (pinfunction "IBN_8") (pintype "unspecified"))
    )
    (net (code "26") (name "IBP") (class "Default")
      (node (ref "C20") (pin "2") (pinfunction "2_2") (pintype "unspecified"))
      (node (ref "R21") (pin "2") (pinfunction "2_2") (pintype "input"))
      (node (ref "U9") (pin "7") (pinfunction "IBP_7") (pintype "unspecified"))
    )
    (net (code "27") (name "ICN") (class "Default")
      (node (ref "C23") (pin "1") (pinfunction "1_1") (pintype "unspecified"))
      (node (ref "R27") (pin "2") (pinfunction "2_2") (pintype "input"))
      (node (ref "U9") (pin "10") (pinfunction "ICN_10") (pintype "unspecified"))
    )
    (net (code "28") (name "ICP") (class "Default")
      (node (ref "C22") (pin "2") (pinfunction "2_2") (pintype "unspecified"))
      (node (ref "R25") (pin "2") (pinfunction "2_2") (pintype "input"))
      (node (ref "U9") (pin "9") (pinfunction "ICP_9") (pintype "unspecified"))
    )
    (net (code "29") (name "IO7") (class "Default")
      (node (ref "U4") (pin "4") (pinfunction "4_4") (pintype "unspecified"))
      (node (ref "U5") (pin "7") (pinfunction "IO7_7") (pintype "unspecified"))
    )
    (net (code "30") (name "IO8") (class "Default")
      (node (ref "U4") (pin "5") (pinfunction "5_5") (pintype "unspecified"))
      (node (ref "U5") (pin "12") (pinfunction "IO8_12") (pintype "unspecified"))
    )
    (net (code "31") (name "IO9") (class "Default")
      (node (ref "U4") (pin "6") (pinfunction "6_6") (pintype "unspecified"))
      (node (ref "U5") (pin "17") (pinfunction "IO9_17") (pintype "unspecified"))
    )
    (net (code "32") (name "IO46") (class "Default")
      (node (ref "R30") (pin "1") (pinfunction "1_1") (pintype "input"))
      (node (ref "U17") (pin "4") (pinfunction "EMITTER_4") (pintype "unspecified"))
      (node (ref "U4") (pin "8") (pinfunction "8_8") (pintype "unspecified"))
      (node (ref "U5") (pin "16") (pinfunction "IO46_16") (pintype "unspecified"))
    )
    (net (code "33") (name "NRST") (class "Default")
      (node (ref "C1") (pin "1") (pinfunction "1_1") (pintype "unspecified"))
      (node (ref "C24") (pin "2") (pinfunction "2_2") (pintype "unspecified"))
      (node (ref "R28") (pin "2") (pinfunction "2_2") (pintype "input"))
      (node (ref "U15") (pin "1") (pinfunction "1_1") (pintype "unspecified"))
      (node (ref "U5") (pin "3") (pinfunction "EN_3") (pintype "unspecified"))
    )
    (net (code "34") (name "Net-(BUZZER--)") (class "Default")
      (node (ref "BUZZER") (pin "1") (pinfunction "-_1") (pintype "unspecified"))
      (node (ref "Q1") (pin "3") (pinfunction "C_3") (pintype "unspecified"))
    )
    (net (code "35") (name "Net-(DEBUG-A)") (class "Default")
      (node (ref "DEBUG") (pin "1") (pinfunction "A_1") (pintype "unspecified"))
      (node (ref "R2") (pin "1") (pinfunction "1_1") (pintype "input"))
    )
    (net (code "36") (name "Net-(J1-Pad1)") (class "Default")
      (node (ref "J1") (pin "1") (pinfunction "1_1") (pintype "bidirectional"))
      (node (ref "R4") (pin "2") (pinfunction "2_2") (pintype "input"))
    )
    (net (code "37") (name "Net-(J2-Pad1)") (class "Default")
      (node (ref "J2") (pin "1") (pinfunction "1_1") (pintype "bidirectional"))
      (node (ref "R11") (pin "2") (pinfunction "2_2") (pintype "input"))
    )
    (net (code "38") (name "Net-(J2-Pad2)") (class "Default")
      (node (ref "J2") (pin "2") (pinfunction "2_2") (pintype "bidirectional"))
      (node (ref "R7") (pin "2") (pinfunction "2_2") (pintype "input"))
    )
    (net (code "39") (name "Net-(J3-Pad2)") (class "Default")
      (node (ref "J3") (pin "2") (pinfunction "2_2") (pintype "bidirectional"))
      (node (ref "R15") (pin "1") (pinfunction "1_1") (pintype "input"))
      (node (ref "R17") (pin "2") (pinfunction "2_2") (pintype "input"))
    )
    (net (code "40") (name "Net-(J4-Pad1)") (class "Default")
      (node (ref "J4") (pin "1") (pinfunction "1_1") (pintype "bidirectional"))
      (node (ref "R21") (pin "1") (pinfunction "1_1") (pintype "input"))
      (node (ref "R22") (pin "2") (pinfunction "2_2") (pintype "input"))
    )
    (net (code "41") (name "Net-(J4-Pad2)") (class "Default")
      (node (ref "J4") (pin "2") (pinfunction "2_2") (pintype "bidirectional"))
      (node (ref "R25") (pin "1") (pinfunction "1_1") (pintype "input"))
      (node (ref "R26") (pin "2") (pinfunction "2_2") (pintype "input"))
    )
    (net (code "42") (name "Net-(JP1-Pad1)") (class "Default")
      (node (ref "JP1") (pin "1") (pinfunction "1_1") (pintype "bidirectional"))
      (node (ref "U13") (pin "1") (pinfunction "1_1") (pintype "unspecified"))
    )
    (net (code "43") (name "Net-(JP1-Pad2)") (class "Default")
      (node (ref "JP1") (pin "2") (pinfunction "2_2") (pintype "bidirectional"))
      (node (ref "U13") (pin "3") (pinfunction "3_3") (pintype "unspecified"))
    )
    (net (code "44") (name "Net-(JP1-Pad3)") (class "Default")
      (node (ref "JP1") (pin "3") (pinfunction "3_3") (pintype "bidirectional"))
      (node (ref "U13") (pin "5") (pinfunction "5_5") (pintype "unspecified"))
    )
    (net (code "45") (name "Net-(JP2-Pad1)") (class "Default")
      (node (ref "JP2") (pin "1") (pinfunction "1_1") (pintype "bidirectional"))
      (node (ref "U16") (pin "1") (pinfunction "1_1") (pintype "unspecified"))
    )
    (net (code "46") (name "Net-(JP2-Pad2)") (class "Default")
      (node (ref "JP2") (pin "2") (pinfunction "2_2") (pintype "bidirectional"))
      (node (ref "U16") (pin "3") (pinfunction "3_3") (pintype "unspecified"))
    )
    (net (code "47") (name "Net-(JP2-Pad3)") (class "Default")
      (node (ref "JP2") (pin "3") (pinfunction "3_3") (pintype "bidirectional"))
      (node (ref "U16") (pin "5") (pinfunction "5_5") (pintype "unspecified"))
    )
    (net (code "48") (name "Net-(JP3-Pad1)") (class "Default")
      (node (ref "JP3") (pin "1") (pinfunction "1_1") (pintype "bidirectional"))
      (node (ref "U18") (pin "1") (pinfunction "1_1") (pintype "unspecified"))
    )
    (net (code "49") (name "Net-(JP3-Pad2)") (class "Default")
      (node (ref "JP3") (pin "2") (pinfunction "2_2") (pintype "bidirectional"))
      (node (ref "U18") (pin "3") (pinfunction "3_3") (pintype "unspecified"))
    )
    (net (code "50") (name "Net-(JP3-Pad3)") (class "Default")
      (node (ref "JP3") (pin "3") (pinfunction "3_3") (pintype "bidirectional"))
      (node (ref "U18") (pin "5") (pinfunction "5_5") (pintype "unspecified"))
    )
    (net (code "51") (name "Net-(POWER-A)") (class "Default")
      (node (ref "POWER") (pin "1") (pinfunction "A_1") (pintype "unspecified"))
      (node (ref "R12") (pin "1") (pinfunction "1_1") (pintype "input"))
    )
    (net (code "52") (name "Net-(Q1-B)") (class "Default")
      (node (ref "Q1") (pin "1") (pinfunction "B_1") (pintype "unspecified"))
      (node (ref "R9") (pin "2") (pinfunction "2_2") (pintype "input"))
    )
    (net (code "53") (name "Net-(Q2-B)") (class "Default")
      (node (ref "Q2") (pin "1") (pinfunction "B_1") (pintype "unspecified"))
      (node (ref "R14") (pin "2") (pinfunction "2_2") (pintype "input"))
    )
    (net (code "54") (name "Net-(Q3-B)") (class "Default")
      (node (ref "Q3") (pin "1") (pinfunction "B_1") (pintype "unspecified"))
      (node (ref "R16") (pin "2") (pinfunction "2_2") (pintype "input"))
    )
    (net (code "55") (name "Net-(Q4-B)") (class "Default")
      (node (ref "Q4") (pin "1") (pinfunction "B_1") (pintype "unspecified"))
      (node (ref "R19") (pin "2") (pinfunction "2_2") (pintype "input"))
    )
    (net (code "56") (name "Net-(R3-Pad2)") (class "Default")
      (node (ref "R3") (pin "2") (pinfunction "2_2") (pintype "input"))
      (node (ref "R4") (pin "1") (pinfunction "1_1") (pintype "input"))
    )
    (net (code "57") (name "Net-(R6-Pad2)") (class "Default")
      (node (ref "R6") (pin "2") (pinfunction "2_2") (pintype "input"))
      (node (ref "R7") (pin "1") (pinfunction "1_1") (pintype "input"))
    )
    (net (code "58") (name "Net-(R10-Pad2)") (class "Default")
      (node (ref "R10") (pin "2") (pinfunction "2_2") (pintype "input"))
      (node (ref "R11") (pin "1") (pinfunction "1_1") (pintype "input"))
    )
    (net (code "59") (name "Net-(U1-DTR)") (class "Default")
      (node (ref "C1") (pin "2") (pinfunction "2_2") (pintype "unspecified"))
      (node (ref "U1") (pin "1") (pinfunction "DTR_1") (pintype "output"))
    )
    (net (code "60") (name "Net-(U17-CATHODE)") (class "Default")
      (node (ref "R29") (pin "2") (pinfunction "2_2") (pintype "input"))
      (node (ref "U17") (pin "2") (pinfunction "CATHODE_2") (pintype "unspecified"))
    )
    (net (code "61") (name "OSC32_N") (class "Default")
      (node (ref "C12") (pin "2") (pinfunction "2_2") (pintype "unspecified"))
      (node (ref "U5") (pin "9") (pinfunction "IO16_9") (pintype "unspecified"))
      (node (ref "Y1") (pin "1") (pinfunction "1_1") (pintype "unspecified"))
    )
    (net (code "62") (name "OSC32_P") (class "Default")
      (node (ref "C11") (pin "2") (pinfunction "2_2") (pintype "unspecified"))
      (node (ref "U5") (pin "8") (pinfunction "IO15_8") (pintype "unspecified"))
      (node (ref "Y1") (pin "2") (pinfunction "2_2") (pintype "unspecified"))
    )
    (net (code "63") (name "REF_IN_OUT") (class "Default")
      (node (ref "C17") (pin "2") (pinfunction "2_2") (pintype "input"))
      (node (ref "C18") (pin "1") (pinfunction "1_1") (pintype "unspecified"))
      (node (ref "U9") (pin "12") (pinfunction "REFINOUT_12") (pintype "unspecified"))
    )
    (net (code "64") (name "RF_BUSY") (class "Default")
      (node (ref "U2") (pin "12") (pinfunction "BUSY_12") (pintype "unspecified"))
      (node (ref "U5") (pin "24") (pinfunction "IO47_24") (pintype "unspecified"))
    )
    (net (code "65") (name "RF_DIO") (class "Default")
      (node (ref "U2") (pin "11") (pinfunction "DIO1_11") (pintype "unspecified"))
      (node (ref "U3") (pin "14") (pinfunction "DIO0_14") (pintype "unspecified"))
      (node (ref "U5") (pin "22") (pinfunction "IO14_22") (pintype "unspecified"))
    )
    (net (code "66") (name "RF_NSS") (class "Default")
      (node (ref "R1") (pin "1") (pinfunction "1_1") (pintype "input"))
      (node (ref "U2") (pin "7") (pinfunction "NSS_7") (pintype "unspecified"))
      (node (ref "U3") (pin "5") (pinfunction "NSS_5") (pintype "unspecified"))
      (node (ref "U5") (pin "18") (pinfunction "IO10_18") (pintype "unspecified"))
    )
    (net (code "67") (name "RF_RST") (class "Default")
      (node (ref "U2") (pin "13") (pinfunction "RESET_13") (pintype "unspecified"))
      (node (ref "U3") (pin "6") (pinfunction "RESET_6") (pintype "unspecified"))
      (node (ref "U5") (pin "23") (pinfunction "IO21_23") (pintype "unspecified"))
    )
    (net (code "68") (name "RLY1") (class "Default")
      (node (ref "R14") (pin "1") (pinfunction "1_1") (pintype "input"))
      (node (ref "U5") (pin "39") (pinfunction "IO1_39") (pintype "unspecified"))
    )
    (net (code "69") (name "RLY2") (class "Default")
      (node (ref "R16") (pin "1") (pinfunction "1_1") (pintype "input"))
      (node (ref "U5") (pin "38") (pinfunction "IO2_38") (pintype "unspecified"))
    )
    (net (code "70") (name "RLY3") (class "Default")
      (node (ref "R19") (pin "1") (pinfunction "1_1") (pintype "input"))
      (node (ref "U5") (pin "28") (pinfunction "IO35_28") (pintype "unspecified"))
    )
    (net (code "71") (name "SPI2_MISO") (class "Default")
      (node (ref "U2") (pin "5") (pinfunction "MISO_5") (pintype "unspecified"))
      (node (ref "U3") (pin "2") (pinfunction "MISO_2") (pintype "unspecified"))
      (node (ref "U5") (pin "20") (pinfunction "IO12_20") (pintype "unspecified"))
    )
    (net (code "72") (name "SPI2_MOSI") (class "Default")
      (node (ref "U2") (pin "6") (pinfunction "MOSI_6") (pintype "unspecified"))
      (node (ref "U3") (pin "3") (pinfunction "MOSI_3") (pintype "unspecified"))
      (node (ref "U5") (pin "19") (pinfunction "IO11_19") (pintype "unspecified"))
    )
    (net (code "73") (name "SPI2_SCK") (class "Default")
      (node (ref "U2") (pin "4") (pinfunction "SCK_4") (pintype "unspecified"))
      (node (ref "U3") (pin "4") (pinfunction "SCK_4") (pintype "unspecified"))
      (node (ref "U5") (pin "21") (pinfunction "IO13_21") (pintype "unspecified"))
    )
    (net (code "74") (name "SPI3_MISO") (class "Default")
      (node (ref "U4") (pin "3") (pinfunction "3_3") (pintype "unspecified"))
      (node (ref "U5") (pin "5") (pinfunction "IO5_5") (pintype "unspecified"))
      (node (ref "U8") (pin "6") (pinfunction "OUTD_6") (pintype "unspecified"))
    )
    (net (code "75") (name "SPI3_MOSI") (class "Default")
      (node (ref "U4") (pin "2") (pinfunction "2_2") (pintype "unspecified"))
      (node (ref "U5") (pin "6") (pinfunction "IO6_6") (pintype "unspecified"))
      (node (ref "U8") (pin "5") (pinfunction "INC_5") (pintype "unspecified"))
    )
    (net (code "76") (name "SPI3_SCK") (class "Default")
      (node (ref "U4") (pin "1") (pinfunction "1_1") (pintype "unspecified"))
      (node (ref "U5") (pin "4") (pinfunction "IO4_4") (pintype "unspecified"))
      (node (ref "U8") (pin "4") (pinfunction "INB_4") (pintype "unspecified"))
    )
    (net (code "77") (name "TCK") (class "Default")
      (node (ref "CN1") (pin "4") (pinfunction "4_4") (pintype "input"))
      (node (ref "U5") (pin "32") (pinfunction "IO39_32") (pintype "unspecified"))
    )
    (net (code "78") (name "TDI") (class "Default")
      (node (ref "CN1") (pin "2") (pinfunction "2_2") (pintype "input"))
      (node (ref "U5") (pin "34") (pinfunction "IO41_34") (pintype "unspecified"))
    )
    (net (code "79") (name "TDO") (class "Default")
      (node (ref "CN1") (pin "3") (pinfunction "3_3") (pintype "input"))
      (node (ref "U5") (pin "33") (pinfunction "IO40_33") (pintype "unspecified"))
    )
    (net (code "80") (name "TMS") (class "Default")
      (node (ref "CN1") (pin "1") (pinfunction "1_1") (pintype "input"))
      (node (ref "U5") (pin "35") (pinfunction "IO42_35") (pintype "unspecified"))
    )
    (net (code "81") (name "UART2_RX") (class "Default")
      (node (ref "U4") (pin "9") (pinfunction "9_9") (pintype "unspecified"))
      (node (ref "U5") (pin "30") (pinfunction "IO37_30") (pintype "unspecified"))
    )
    (net (code "82") (name "UART2_TX") (class "Default")
      (node (ref "U4") (pin "10") (pinfunction "10_10") (pintype "unspecified"))
      (node (ref "U5") (pin "29") (pinfunction "IO36_29") (pintype "unspecified"))
    )
    (net (code "83") (name "UART_RX") (class "Default")
      (node (ref "U1") (pin "2") (pinfunction "RX_2") (pintype "input"))
      (node (ref "U5") (pin "36") (pinfunction "RXD0_36") (pintype "unspecified"))
    )
    (net (code "84") (name "UART_TX") (class "Default")
      (node (ref "U1") (pin "3") (pinfunction "TX_3") (pintype "output"))
      (node (ref "U5") (pin "37") (pinfunction "TXD0_37") (pintype "unspecified"))
    )
    (net (code "85") (name "USB_D+") (class "Default")
      (node (ref "CN3") (pin "2") (pinfunction "2_2") (pintype "input"))
      (node (ref "U5") (pin "14") (pinfunction "IO20_14") (pintype "unspecified"))
      (node (ref "USB1") (pin "3") (pinfunction "D+_3") (pintype "input"))
    )
    (net (code "86") (name "USB_D-") (class "Default")
      (node (ref "CN3") (pin "3") (pinfunction "3_3") (pintype "input"))
      (node (ref "U5") (pin "13") (pinfunction "IO19_13") (pintype "unspecified"))
      (node (ref "USB1") (pin "2") (pinfunction "D-_2") (pintype "input"))
    )
    (net (code "87") (name "USB_ID") (class "Default")
      (node (ref "TP1") (pin "1") (pinfunction "1_1") (pintype "unspecified"))
      (node (ref "USB1") (pin "4") (pinfunction "ID_4") (pintype "input"))
    )
    (net (code "88") (name "VAP") (class "Default")
      (node (ref "C2") (pin "2") (pinfunction "2_2") (pintype "unspecified"))
      (node (ref "D1") (pin "2") (pinfunction "2_2") (pintype "unspecified"))
      (node (ref "R3") (pin "1") (pinfunction "1_1") (pintype "input"))
      (node (ref "R5") (pin "2") (pinfunction "2_2") (pintype "input"))
      (node (ref "U9") (pin "16") (pinfunction "VAP_16") (pintype "unspecified"))
    )
    (net (code "89") (name "VBP") (class "Default")
      (node (ref "C7") (pin "2") (pinfunction "2_2") (pintype "unspecified"))
      (node (ref "D2") (pin "2") (pinfunction "2_2") (pintype "unspecified"))
      (node (ref "R6") (pin "1") (pinfunction "1_1") (pintype "input"))
      (node (ref "R8") (pin "2") (pinfunction "2_2") (pintype "input"))
      (node (ref "U9") (pin "15") (pinfunction "VBP_15") (pintype "unspecified"))
    )
    (net (code "90") (name "VCP") (class "Default")
      (node (ref "C10") (pin "2") (pinfunction "2_2") (pintype "unspecified"))
      (node (ref "D3") (pin "2") (pinfunction "2_2") (pintype "unspecified"))
      (node (ref "R10") (pin "1") (pinfunction "1_1") (pintype "input"))
      (node (ref "R13") (pin "2") (pinfunction "2_2") (pintype "input"))
      (node (ref "U9") (pin "14") (pinfunction "VCP_14") (pintype "unspecified"))
    )
    (net (code "91") (name "VN") (class "Default")
      (node (ref "C19") (pin "2") (pinfunction "2_2") (pintype "unspecified"))
      (node (ref "R20") (pin "2") (pinfunction "2_2") (pintype "input"))
      (node (ref "U9") (pin "13") (pinfunction "VN_13") (pintype "unspecified"))
    )
    (net (code "92") (name "unconnected-(U2-DIO3-Pad9)") (class "Default")
      (node (ref "U2") (pin "9") (pinfunction "DIO3_9") (pintype "unspecified+no_connect"))
    )
    (net (code "93") (name "unconnected-(U2-NC-Pad2)") (class "Default")
      (node (ref "U2") (pin "2") (pinfunction "NC_2") (pintype "unspecified+no_connect"))
    )
    (net (code "94") (name "unconnected-(U2-NC-Pad3)") (class "Default")
      (node (ref "U2") (pin "3") (pinfunction "NC_3") (pintype "unspecified+no_connect"))
    )
    (net (code "95") (name "unconnected-(U2-NC-Pad10)") (class "Default")
      (node (ref "U2") (pin "10") (pinfunction "NC_10") (pintype "unspecified+no_connect"))
    )
    (net (code "96") (name "unconnected-(U3-DIO1-Pad15)") (class "Default")
      (node (ref "U3") (pin "15") (pinfunction "DIO1_15") (pintype "unspecified+no_connect"))
    )
    (net (code "97") (name "unconnected-(U3-DIO2-Pad16)") (class "Default")
      (node (ref "U3") (pin "16") (pinfunction "DIO2_16") (pintype "unspecified+no_connect"))
    )
    (net (code "98") (name "unconnected-(U3-DIO3-Pad11)") (class "Default")
      (node (ref "U3") (pin "11") (pinfunction "DIO3_11") (pintype "unspecified+no_connect"))
    )
    (net (code "99") (name "unconnected-(U3-DIO4-Pad12)") (class "Default")
      (node (ref "U3") (pin "12") (pinfunction "DIO4_12") (pintype "unspecified+no_connect"))
    )
    (net (code "100") (name "unconnected-(U3-DIO5-Pad7)") (class "Default")
      (node (ref "U3") (pin "7") (pinfunction "DIO5_7") (pintype "unspecified+no_connect"))
    )
    (net (code "101") (name "unconnected-(U5-IO45-Pad26)") (class "Default")
      (node (ref "U5") (pin "26") (pinfunction "IO45_26") (pintype "unspecified"))
    )
    (net (code "102") (name "unconnected-(U9-APCF-Pad1)") (class "Default")
      (node (ref "U9") (pin "1") (pinfunction "APCF_1") (pintype "unspecified"))
    )
    (net (code "103") (name "unconnected-(U9-VARCF-Pad17)") (class "Default")
      (node (ref "U9") (pin "17") (pinfunction "VARCF_17") (pintype "unspecified"))
    )
    (net (code "104") (name "unconnected-(U17-BASE-Pad6)") (class "Default")
      (node (ref "U17") (pin "6") (pinfunction "BASE_6") (pintype "unspecified+no_connect"))
    )
    (net (code "105") (name "unconnected-(U17-NC-Pad3)") (class "Default")
      (node (ref "U17") (pin "3") (pinfunction "NC_3") (pintype "unspecified+no_connect"))
    )
  )
)
